# Sensor10.net
KiCad netlist of a schematic drawn in Altium Designer
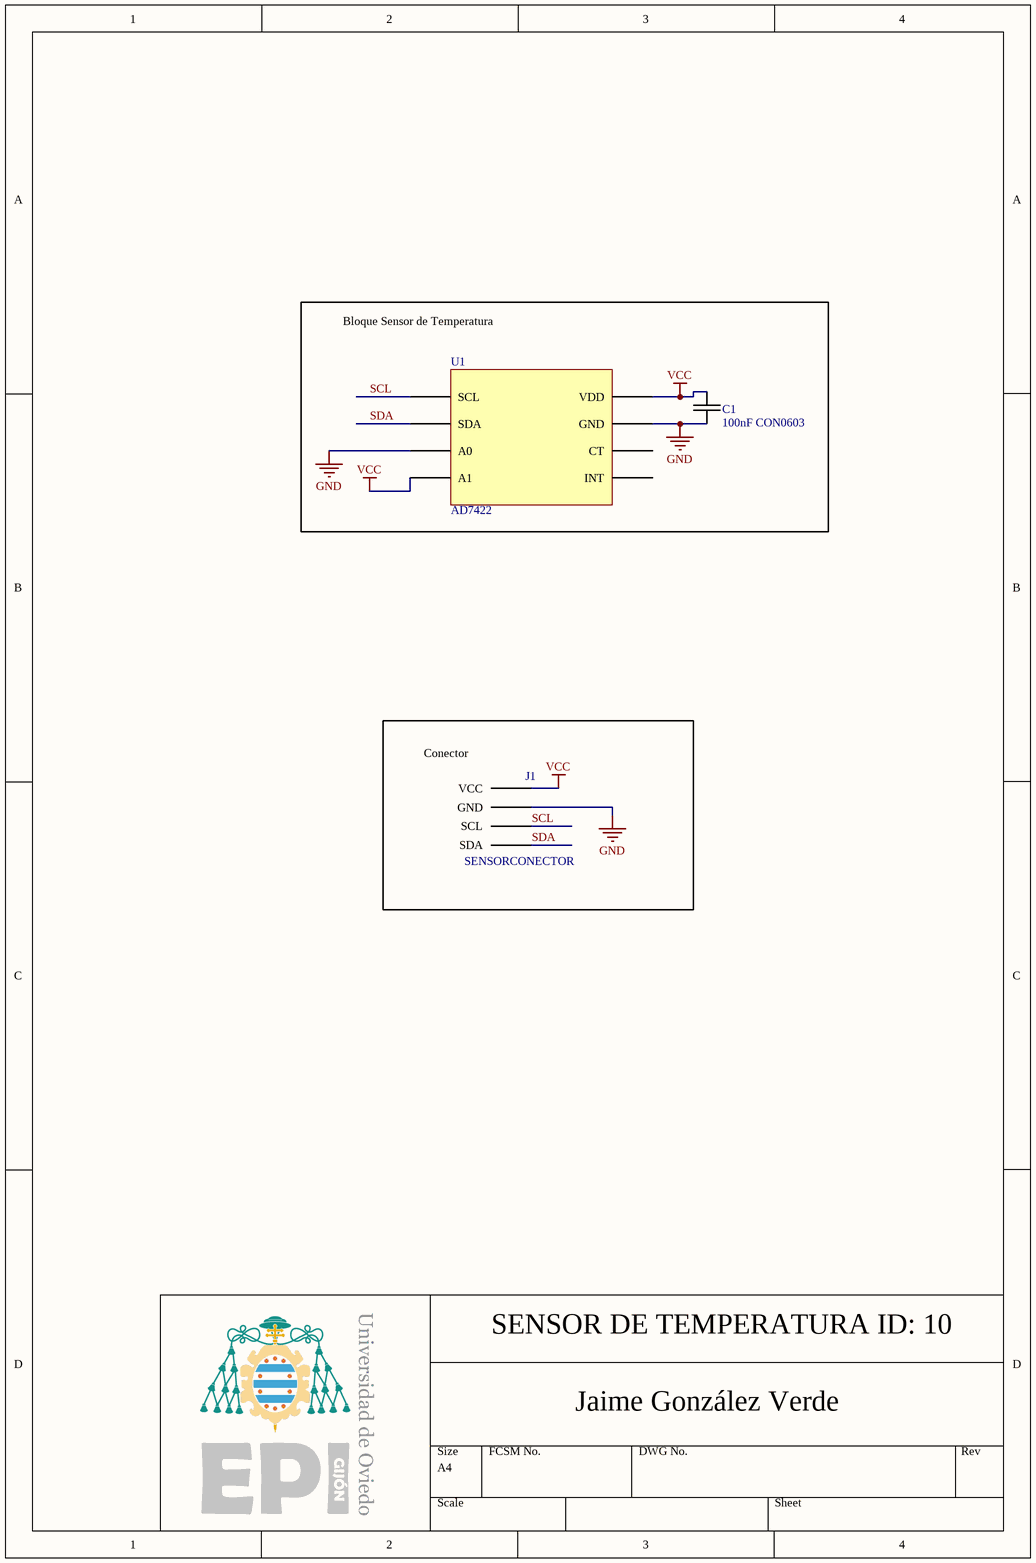
[diagram p0: Sensor10.SchDoc]

(export (version "E")
  (design (tool "Eeschema 10.0.6"))
  (components
    (comp (ref "C1")
      (value "100nF CON0603")
      (footprint "CAPC0603X06N")
      (libsource (lib "JaimeGlez") (part "CON0603"))
    )
    (comp (ref "J1")
      (value "SENSORCONECTOR")
      (footprint "ConectorSMD1,3mm")
      (libsource (lib "JaimeGlez") (part "SENSORCONECTOR"))
    )
    (comp (ref "U1") (value "AD7422") (footprint "ADT7422") (libsource (lib "JaimeGlez") (part "AD7422")))
  )
  (nets
    (net (code "1") (name "/SCL") (class "Default")
      (node (ref "J1") (pin "1") (pinfunction "SCL_1") (pintype "passive"))
      (node (ref "U1") (pin "1") (pinfunction "SCL_1") (pintype "passive"))
    )
    (net (code "2") (name "/SDA") (class "Default")
      (node (ref "J1") (pin "0") (pinfunction "SDA_0") (pintype "passive"))
      (node (ref "U1") (pin "2") (pinfunction "SDA_2") (pintype "passive"))
    )
    (net (code "3") (name "GND") (class "Default")
      (node (ref "C1") (pin "2") (pintype "passive"))
      (node (ref "J1") (pin "2") (pinfunction "GND_2") (pintype "passive"))
      (node (ref "U1") (pin "11") (pinfunction "GND_11") (pintype "passive"))
      (node (ref "U1") (pin "3") (pinfunction "A0_3") (pintype "passive"))
    )
    (net (code "4") (name "VCC") (class "Default")
      (node (ref "C1") (pin "1") (pintype "passive"))
      (node (ref "J1") (pin "3") (pinfunction "VCC_3") (pintype "passive"))
      (node (ref "U1") (pin "12") (pinfunction "VDD_12") (pintype "passive"))
      (node (ref "U1") (pin "4") (pinfunction "A1_4") (pintype "passive"))
    )
    (net (code "5") (name "unconnected-(U1-CT-Pad10)") (class "Default")
      (node (ref "U1") (pin "10") (pinfunction "CT_10") (pintype "passive"))
    )
    (net (code "6") (name "unconnected-(U1-INT-Pad9)") (class "Default")
      (node (ref "U1") (pin "9") (pinfunction "INT_9") (pintype "passive"))
    )
  )
)
